# recnt.net
KiCad netlist of a schematic drawn in EAGLE
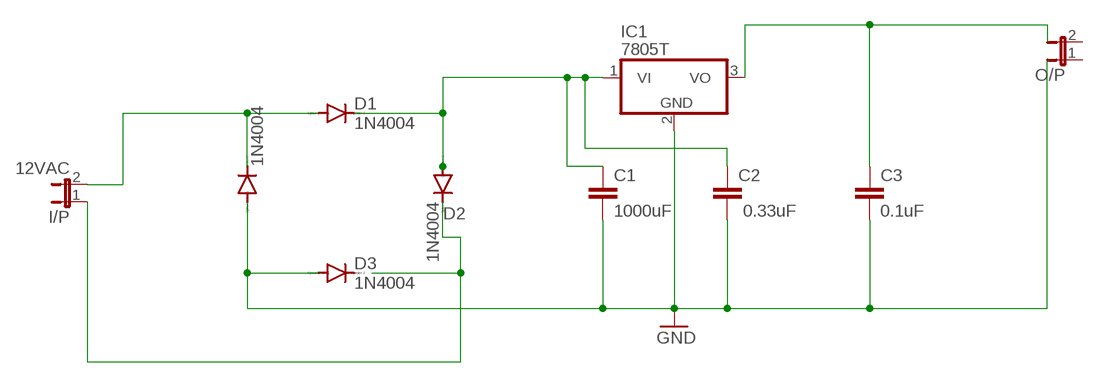
[diagram p0: schematic, sheet 1]

(export (version "E")
  (design (tool "Eeschema 10.0.6"))
  (components
    (comp (ref "C1")
      (value "1000uF")
      (footprint "eagle-import:C2.5-3")
      (libsource (lib "eagle-import") (part "C2,5-3"))
    )
    (comp (ref "C2")
      (value "0.33uF")
      (footprint "eagle-import:C2.5-3")
      (libsource (lib "eagle-import") (part "C2,5-3"))
    )
    (comp (ref "C3")
      (value "0.1uF")
      (footprint "eagle-import:C2.5-3")
      (libsource (lib "eagle-import") (part "C2,5-3"))
    )
    (comp (ref "D1")
      (value "1N4004")
      (footprint "eagle-import:DO41-10")
      (libsource (lib "eagle-import") (part "1N4004"))
    )
    (comp (ref "D2")
      (value "1N4004")
      (footprint "eagle-import:DO41-10")
      (libsource (lib "eagle-import") (part "1N4004"))
    )
    (comp (ref "D3")
      (value "1N4004")
      (footprint "eagle-import:DO41-10")
      (libsource (lib "eagle-import") (part "1N4004"))
    )
    (comp (ref "D4")
      (value "1N4004")
      (footprint "eagle-import:DO41-10")
      (libsource (lib "eagle-import") (part "1N4004"))
    )
    (comp (ref "I/P")
      (value "12VAC")
      (footprint "eagle-import:JP1")
      (libsource (lib "eagle-import") (part "JP1E"))
    )
    (comp (ref "IC1")
      (value "7805T")
      (footprint "eagle-import:TO220H")
      (libsource (lib "eagle-import") (part "78T05"))
    )
    (comp (ref "O/P")
      (value "JP1E")
      (footprint "eagle-import:JP1")
      (libsource (lib "eagle-import") (part "JP1E"))
    )
  )
  (nets
    (net (code "1") (name "/D2") (class "Default")
      (node (ref "D2") (pin "C") (pinfunction "C_C") (pintype "passive"))
      (node (ref "I/P") (pin "1") (pinfunction "1_1") (pintype "passive"))
    )
    (net (code "2") (name "GND") (class "Default")
      (node (ref "C1") (pin "2") (pinfunction "2_2") (pintype "passive"))
      (node (ref "C2") (pin "2") (pinfunction "2_2") (pintype "passive"))
      (node (ref "C3") (pin "2") (pinfunction "2_2") (pintype "passive"))
      (node (ref "D3") (pin "A") (pinfunction "A_A") (pintype "passive"))
      (node (ref "D4") (pin "A") (pinfunction "A_A") (pintype "passive"))
      (node (ref "IC1") (pin "2") (pinfunction "GND_2") (pintype "passive"))
    )
    (net (code "3") (name "Net-(D1-PadA)") (class "Default")
      (node (ref "D1") (pin "A") (pinfunction "A_A") (pintype "passive"))
      (node (ref "D4") (pin "C") (pinfunction "C_C") (pintype "passive"))
      (node (ref "I/P") (pin "2") (pinfunction "2_2") (pintype "passive"))
    )
    (net (code "4") (name "Net-(IC1-VI)") (class "Default")
      (node (ref "C1") (pin "1") (pinfunction "1_1") (pintype "passive"))
      (node (ref "C2") (pin "1") (pinfunction "1_1") (pintype "passive"))
      (node (ref "D1") (pin "C") (pinfunction "C_C") (pintype "passive"))
      (node (ref "D2") (pin "A") (pinfunction "A_A") (pintype "passive"))
      (node (ref "IC1") (pin "1") (pinfunction "VI_1") (pintype "input"))
    )
    (net (code "5") (name "Net-(IC1-VO)") (class "Default")
      (node (ref "C3") (pin "1") (pinfunction "1_1") (pintype "passive"))
      (node (ref "IC1") (pin "3") (pinfunction "VO_3") (pintype "passive"))
    )
    (net (code "6") (name "unconnected-(D3-PadC)") (class "Default")
      (node (ref "D3") (pin "C") (pinfunction "C_C") (pintype "passive"))
    )
    (net (code "7") (name "unconnected-(O/P-Pad1)") (class "Default")
      (node (ref "O/P") (pin "1") (pinfunction "1_1") (pintype "passive"))
    )
    (net (code "8") (name "unconnected-(O/P-Pad2)") (class "Default")
      (node (ref "O/P") (pin "2") (pinfunction "2_2") (pintype "passive"))
    )
  )
)
